# main.net
KiCad netlist of a schematic drawn in EAGLE
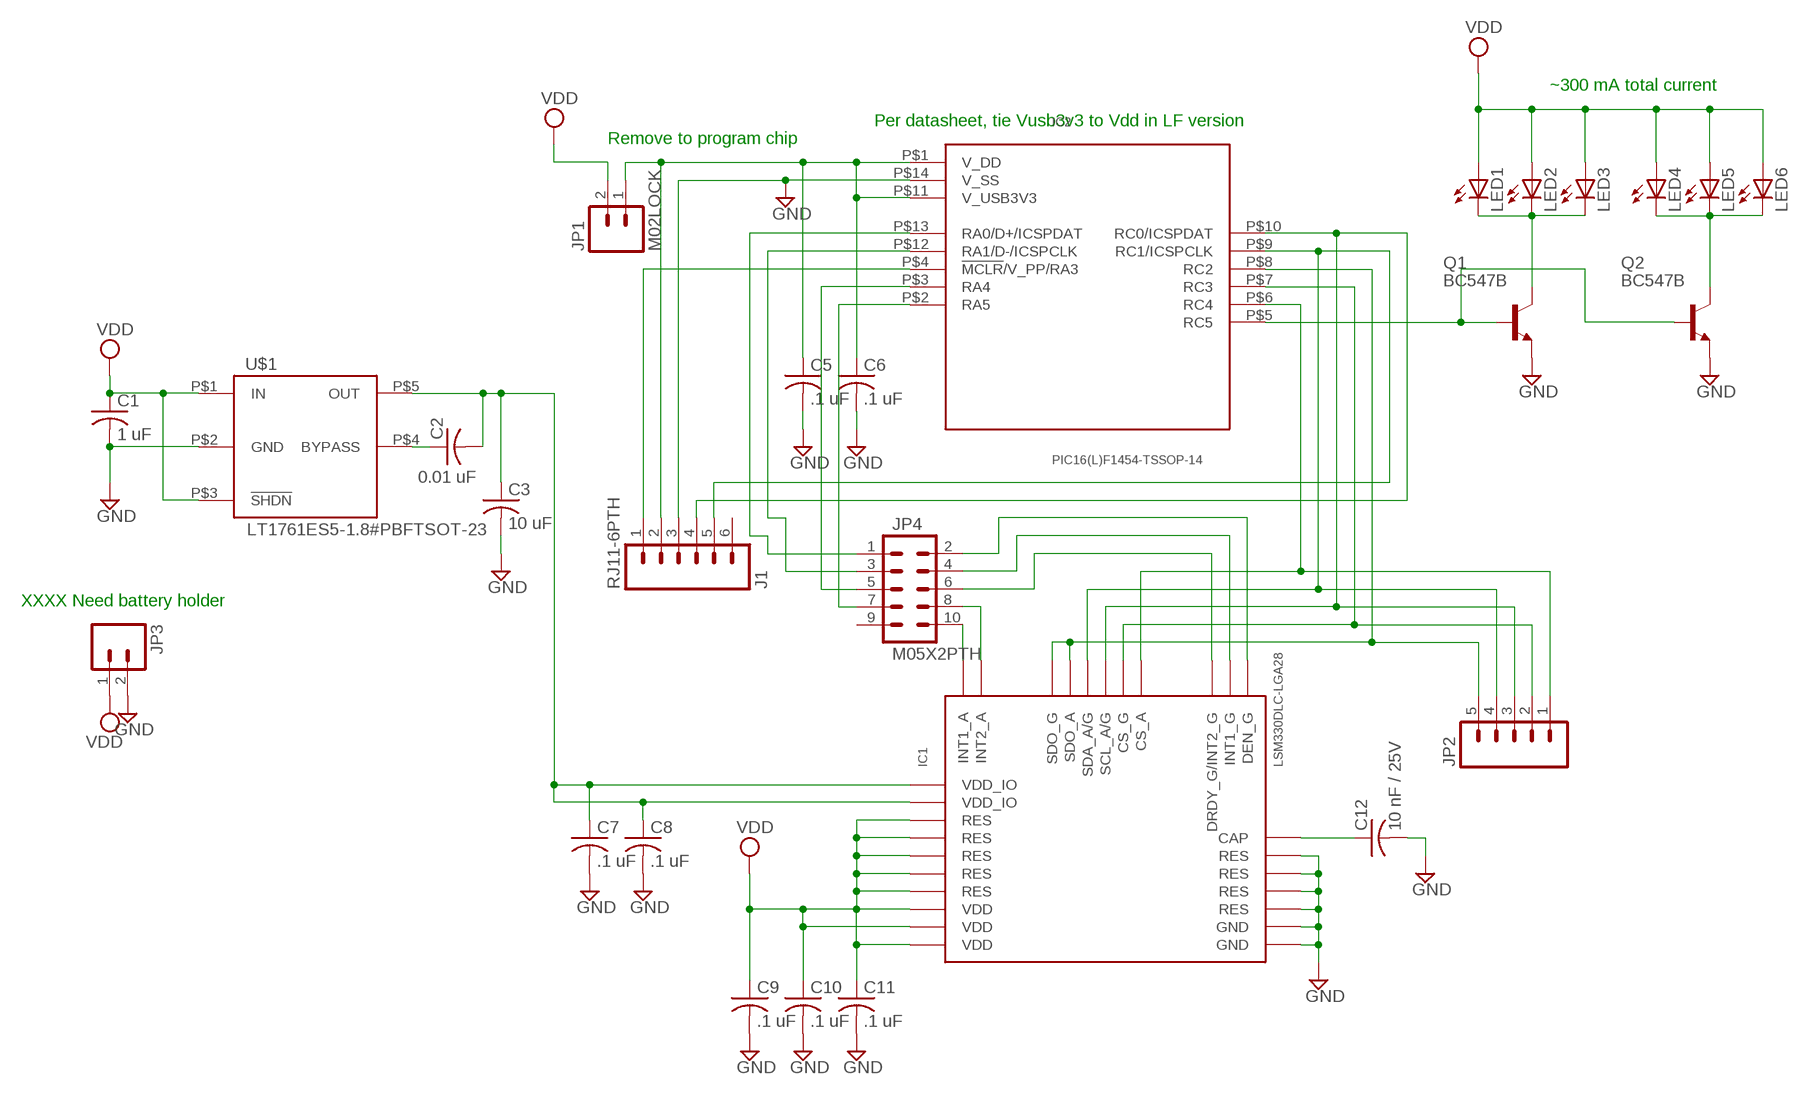
[diagram p0: schematic, sheet 1]

(export (version "E")
  (design (tool "Eeschema 10.0.6"))
  (components
    (comp (ref "C1")
      (value "1 uF")
      (footprint "eagle-import:C1206")
      (libsource (lib "eagle-import") (part "C-USC1206"))
    )
    (comp (ref "C2")
      (value "0.01 uF")
      (footprint "eagle-import:C1206")
      (libsource (lib "eagle-import") (part "C-USC1206"))
    )
    (comp (ref "C3")
      (value "10 uF")
      (footprint "eagle-import:C1206")
      (libsource (lib "eagle-import") (part "C-USC1206"))
    )
    (comp (ref "C5")
      (value ".1 uF")
      (footprint "eagle-import:C1206")
      (libsource (lib "eagle-import") (part "C-USC1206"))
    )
    (comp (ref "C6")
      (value ".1 uF")
      (footprint "eagle-import:C1206")
      (libsource (lib "eagle-import") (part "C-USC1206"))
    )
    (comp (ref "C7")
      (value ".1 uF")
      (footprint "eagle-import:C1206")
      (libsource (lib "eagle-import") (part "C-USC1206"))
    )
    (comp (ref "C8")
      (value ".1 uF")
      (footprint "eagle-import:C1206")
      (libsource (lib "eagle-import") (part "C-USC1206"))
    )
    (comp (ref "C9")
      (value ".1 uF")
      (footprint "eagle-import:C1206")
      (libsource (lib "eagle-import") (part "C-USC1206"))
    )
    (comp (ref "C10")
      (value ".1 uF")
      (footprint "eagle-import:C1206")
      (libsource (lib "eagle-import") (part "C-USC1206"))
    )
    (comp (ref "C11")
      (value ".1 uF")
      (footprint "eagle-import:C1206")
      (libsource (lib "eagle-import") (part "C-USC1206"))
    )
    (comp (ref "C12")
      (value "10 nF / 25V")
      (footprint "eagle-import:C1206")
      (libsource (lib "eagle-import") (part "C-USC1206"))
    )
    (comp (ref "IC1")
      (value "LSM330DLC-LGA28")
      (footprint "eagle-import:LGA-28")
      (libsource (lib "eagle-import") (part "LSM330DLC-LGA28"))
    )
    (comp (ref "IC2")
      (value "PIC16(L)F1454-TSSOP-14")
      (footprint "eagle-import:TSSOP-14")
      (libsource (lib "eagle-import") (part "PIC16(L)F1454-TSSOP-14"))
    )
    (comp (ref "J1")
      (value "RJ11-6PTH")
      (footprint "eagle-import:RJ11-6")
      (libsource (lib "eagle-import") (part "RJ11-6PTH"))
    )
    (comp (ref "JP1")
      (value "M02LOCK")
      (footprint "eagle-import:1X02_LOCK")
      (libsource (lib "eagle-import") (part "M02LOCK"))
    )
    (comp (ref "JP2")
      (value "M05PTH")
      (footprint "eagle-import:1X05")
      (libsource (lib "eagle-import") (part "M05PTH"))
    )
    (comp (ref "JP3")
      (value "M02LOCK")
      (footprint "eagle-import:1X02_LOCK")
      (libsource (lib "eagle-import") (part "M02LOCK"))
    )
    (comp (ref "JP4")
      (value "M05X2PTH")
      (footprint "eagle-import:AVR_ICSP")
      (libsource (lib "eagle-import") (part "M05X2PTH"))
    )
    (comp (ref "LED1")
      (value "LED5MM")
      (footprint "eagle-import:LED5MM")
      (libsource (lib "eagle-import") (part "LED5MM"))
    )
    (comp (ref "LED2")
      (value "LED5MM")
      (footprint "eagle-import:LED5MM")
      (libsource (lib "eagle-import") (part "LED5MM"))
    )
    (comp (ref "LED3")
      (value "LED5MM")
      (footprint "eagle-import:LED5MM")
      (libsource (lib "eagle-import") (part "LED5MM"))
    )
    (comp (ref "LED4")
      (value "LED5MM")
      (footprint "eagle-import:LED5MM")
      (libsource (lib "eagle-import") (part "LED5MM"))
    )
    (comp (ref "LED5")
      (value "LED5MM")
      (footprint "eagle-import:LED5MM")
      (libsource (lib "eagle-import") (part "LED5MM"))
    )
    (comp (ref "LED6")
      (value "LED5MM")
      (footprint "eagle-import:LED5MM")
      (libsource (lib "eagle-import") (part "LED5MM"))
    )
    (comp (ref "Q1")
      (value "BC547B")
      (footprint "eagle-import:TO92")
      (libsource (lib "eagle-import") (part "BC547B"))
    )
    (comp (ref "Q2")
      (value "BC547B")
      (footprint "eagle-import:TO92")
      (libsource (lib "eagle-import") (part "BC547B"))
    )
    (comp (ref "U$1")
      (value "LT1761ES5-1.8#PBFTSOT-23")
      (footprint "eagle-import:TSOT-23")
      (libsource (lib "eagle-import") (part "LT1761ES5-1.8#PBFTSOT-23"))
    )
  )
  (nets
    (net (code "1") (name "GND") (class "Default")
      (node (ref "C1") (pin "2") (pinfunction "2_2") (pintype "passive"))
      (node (ref "C10") (pin "2") (pinfunction "2_2") (pintype "passive"))
      (node (ref "C11") (pin "2") (pinfunction "2_2") (pintype "passive"))
      (node (ref "C12") (pin "2") (pinfunction "2_2") (pintype "passive"))
      (node (ref "C3") (pin "2") (pinfunction "2_2") (pintype "passive"))
      (node (ref "C5") (pin "2") (pinfunction "2_2") (pintype "passive"))
      (node (ref "C6") (pin "2") (pinfunction "2_2") (pintype "passive"))
      (node (ref "C7") (pin "2") (pinfunction "2_2") (pintype "passive"))
      (node (ref "C8") (pin "2") (pinfunction "2_2") (pintype "passive"))
      (node (ref "C9") (pin "2") (pinfunction "2_2") (pintype "passive"))
      (node (ref "IC1") (pin "P$1") (pinfunction "GND_P$1") (pintype "power_in"))
      (node (ref "IC1") (pin "P$2") (pinfunction "RES_P$2") (pintype "power_in"))
      (node (ref "IC1") (pin "P$3") (pinfunction "RES_P$3") (pintype "power_in"))
      (node (ref "IC1") (pin "P$4") (pinfunction "RES_P$4") (pintype "power_in"))
      (node (ref "IC1") (pin "P$5") (pinfunction "RES_P$5") (pintype "power_in"))
      (node (ref "IC1") (pin "P$6") (pinfunction "GND_P$6") (pintype "power_in"))
      (node (ref "IC2") (pin "P$14") (pinfunction "V_SS_P$14") (pintype "power_in"))
      (node (ref "J1") (pin "3") (pinfunction "3_3") (pintype "passive"))
      (node (ref "JP3") (pin "2") (pinfunction "2_2") (pintype "passive"))
      (node (ref "Q1") (pin "1") (pinfunction "E_1") (pintype "passive"))
      (node (ref "Q2") (pin "1") (pinfunction "E_1") (pintype "passive"))
      (node (ref "U$1") (pin "P$2") (pinfunction "GND_P$2") (pintype "power_in"))
    )
    (net (code "2") (name "Net-(IC1-CAP)") (class "Default")
      (node (ref "C12") (pin "1") (pinfunction "1_1") (pintype "passive"))
      (node (ref "IC1") (pin "P$15") (pinfunction "CAP_P$15") (pintype "passive"))
    )
    (net (code "3") (name "Net-(IC1-CS_A)") (class "Default")
      (node (ref "IC1") (pin "P$23") (pinfunction "CS_A_P$23") (pintype "bidirectional"))
      (node (ref "IC2") (pin "P$6") (pinfunction "RC4_P$6") (pintype "bidirectional"))
      (node (ref "JP2") (pin "1") (pinfunction "1_1") (pintype "passive"))
    )
    (net (code "4") (name "Net-(IC1-CS_G)") (class "Default")
      (node (ref "IC1") (pin "P$22") (pinfunction "CS_G_P$22") (pintype "bidirectional"))
      (node (ref "IC2") (pin "P$7") (pinfunction "RC3_P$7") (pintype "bidirectional"))
      (node (ref "JP2") (pin "2") (pinfunction "2_2") (pintype "passive"))
    )
    (net (code "5") (name "Net-(IC1-DEN_G)") (class "Default")
      (node (ref "IC1") (pin "P$16") (pinfunction "DEN_G_P$16") (pintype "bidirectional"))
      (node (ref "JP4") (pin "2") (pinfunction "2_2") (pintype "passive"))
    )
    (net (code "6") (name "Net-(IC1-DRDY_G{slash}INT2_G)") (class "Default")
      (node (ref "IC1") (pin "P$17") (pinfunction "DRDY_G/INT2_G_P$17") (pintype "bidirectional"))
      (node (ref "JP4") (pin "6") (pinfunction "6_6") (pintype "passive"))
    )
    (net (code "7") (name "Net-(IC1-INT1_A)") (class "Default")
      (node (ref "IC1") (pin "P$20") (pinfunction "INT1_A_P$20") (pintype "bidirectional"))
      (node (ref "JP4") (pin "10") (pinfunction "10_10") (pintype "passive"))
    )
    (net (code "8") (name "Net-(IC1-INT1_G)") (class "Default")
      (node (ref "IC1") (pin "P$18") (pinfunction "INT1_G_P$18") (pintype "bidirectional"))
      (node (ref "JP4") (pin "4") (pinfunction "4_4") (pintype "passive"))
    )
    (net (code "9") (name "Net-(IC1-INT2_A)") (class "Default")
      (node (ref "IC1") (pin "P$19") (pinfunction "INT2_A_P$19") (pintype "bidirectional"))
      (node (ref "JP4") (pin "8") (pinfunction "8_8") (pintype "passive"))
    )
    (net (code "10") (name "Net-(IC1-SCL_A{slash}G)") (class "Default")
      (node (ref "IC1") (pin "P$24") (pinfunction "SCL_A/G_P$24") (pintype "bidirectional"))
      (node (ref "IC2") (pin "P$10") (pinfunction "RC0/ICSPDAT_P$10") (pintype "bidirectional"))
      (node (ref "J1") (pin "4") (pinfunction "4_4") (pintype "passive"))
      (node (ref "JP2") (pin "3") (pinfunction "3_3") (pintype "passive"))
    )
    (net (code "11") (name "Net-(IC1-SDA_A{slash}G)") (class "Default")
      (node (ref "IC1") (pin "P$28") (pinfunction "SDA_A/G_P$28") (pintype "bidirectional"))
      (node (ref "IC2") (pin "P$9") (pinfunction "RC1/ICSPCLK_P$9") (pintype "bidirectional"))
      (node (ref "J1") (pin "5") (pinfunction "5_5") (pintype "passive"))
      (node (ref "JP2") (pin "4") (pinfunction "4_4") (pintype "passive"))
    )
    (net (code "12") (name "Net-(IC1-SDO_A)") (class "Default")
      (node (ref "IC1") (pin "P$26") (pinfunction "SDO_G_P$26") (pintype "bidirectional"))
      (node (ref "IC1") (pin "P$27") (pinfunction "SDO_A_P$27") (pintype "bidirectional"))
      (node (ref "IC2") (pin "P$8") (pinfunction "RC2_P$8") (pintype "bidirectional"))
      (node (ref "JP2") (pin "5") (pinfunction "5_5") (pintype "passive"))
    )
    (net (code "13") (name "Net-(IC2-RA0{slash}D+{slash}ICSPDAT)") (class "Default")
      (node (ref "IC2") (pin "P$13") (pinfunction "RA0/D+/ICSPDAT_P$13") (pintype "bidirectional"))
      (node (ref "JP4") (pin "1") (pinfunction "1_1") (pintype "passive"))
    )
    (net (code "14") (name "Net-(IC2-RA1{slash}D-{slash}ICSPCLK)") (class "Default")
      (node (ref "IC2") (pin "P$12") (pinfunction "RA1/D-/ICSPCLK_P$12") (pintype "bidirectional"))
      (node (ref "JP4") (pin "3") (pinfunction "3_3") (pintype "passive"))
    )
    (net (code "15") (name "Net-(IC2-RA4)") (class "Default")
      (node (ref "IC2") (pin "P$3") (pinfunction "RA4_P$3") (pintype "bidirectional"))
      (node (ref "JP4") (pin "5") (pinfunction "5_5") (pintype "passive"))
    )
    (net (code "16") (name "Net-(IC2-RA5)") (class "Default")
      (node (ref "IC2") (pin "P$2") (pinfunction "RA5_P$2") (pintype "bidirectional"))
      (node (ref "JP4") (pin "7") (pinfunction "7_7") (pintype "passive"))
    )
    (net (code "17") (name "Net-(IC2-RC5)") (class "Default")
      (node (ref "IC2") (pin "P$5") (pinfunction "RC5_P$5") (pintype "bidirectional"))
      (node (ref "Q1") (pin "2") (pinfunction "B_2") (pintype "passive"))
      (node (ref "Q2") (pin "2") (pinfunction "B_2") (pintype "passive"))
    )
    (net (code "18") (name "Net-(IC2-V_DD)") (class "Default")
      (node (ref "C5") (pin "1") (pinfunction "1_1") (pintype "passive"))
      (node (ref "C6") (pin "1") (pinfunction "1_1") (pintype "passive"))
      (node (ref "IC2") (pin "P$1") (pinfunction "V_DD_P$1") (pintype "power_in"))
      (node (ref "IC2") (pin "P$11") (pinfunction "V_USB3V3_P$11") (pintype "power_in"))
      (node (ref "J1") (pin "2") (pinfunction "2_2") (pintype "passive"))
      (node (ref "JP1") (pin "1") (pinfunction "1_1") (pintype "passive"))
    )
    (net (code "19") (name "Net-(IC2-~{MCLR}{slash}V_PP{slash}RA3)") (class "Default")
      (node (ref "IC2") (pin "P$4") (pinfunction "~{MCLR}/V_PP/RA3_P$4") (pintype "bidirectional"))
      (node (ref "J1") (pin "1") (pinfunction "1_1") (pintype "passive"))
    )
    (net (code "20") (name "Net-(LED1-C)") (class "Default")
      (node (ref "LED1") (pin "K") (pinfunction "C_K") (pintype "passive"))
      (node (ref "LED2") (pin "K") (pinfunction "C_K") (pintype "passive"))
      (node (ref "LED3") (pin "K") (pinfunction "C_K") (pintype "passive"))
      (node (ref "Q1") (pin "3") (pinfunction "C_3") (pintype "passive"))
    )
    (net (code "21") (name "Net-(LED4-C)") (class "Default")
      (node (ref "LED4") (pin "K") (pinfunction "C_K") (pintype "passive"))
      (node (ref "LED5") (pin "K") (pinfunction "C_K") (pintype "passive"))
      (node (ref "LED6") (pin "K") (pinfunction "C_K") (pintype "passive"))
      (node (ref "Q2") (pin "3") (pinfunction "C_3") (pintype "passive"))
    )
    (net (code "22") (name "Net-(U$1-BYPASS)") (class "Default")
      (node (ref "C2") (pin "1") (pinfunction "1_1") (pintype "passive"))
      (node (ref "U$1") (pin "P$4") (pinfunction "BYPASS_P$4") (pintype "output"))
    )
    (net (code "23") (name "Net-(U$1-OUT)") (class "Default")
      (node (ref "C2") (pin "2") (pinfunction "2_2") (pintype "passive"))
      (node (ref "C3") (pin "1") (pinfunction "1_1") (pintype "passive"))
      (node (ref "C7") (pin "1") (pinfunction "1_1") (pintype "passive"))
      (node (ref "C8") (pin "1") (pinfunction "1_1") (pintype "passive"))
      (node (ref "IC1") (pin "P$21") (pinfunction "VDD_IO_P$21") (pintype "power_in"))
      (node (ref "IC1") (pin "P$25") (pinfunction "VDD_IO_P$25") (pintype "bidirectional"))
      (node (ref "U$1") (pin "P$5") (pinfunction "OUT_P$5") (pintype "power_in"))
    )
    (net (code "24") (name "VDD") (class "Default")
      (node (ref "C1") (pin "1") (pinfunction "1_1") (pintype "passive"))
      (node (ref "C10") (pin "1") (pinfunction "1_1") (pintype "passive"))
      (node (ref "C11") (pin "1") (pinfunction "1_1") (pintype "passive"))
      (node (ref "C9") (pin "1") (pinfunction "1_1") (pintype "passive"))
      (node (ref "IC1") (pin "P$10") (pinfunction "RES_P$10") (pintype "power_in"))
      (node (ref "IC1") (pin "P$11") (pinfunction "RES_P$11") (pintype "power_in"))
      (node (ref "IC1") (pin "P$12") (pinfunction "RES_P$12") (pintype "power_in"))
      (node (ref "IC1") (pin "P$13") (pinfunction "RES_P$13") (pintype "power_in"))
      (node (ref "IC1") (pin "P$14") (pinfunction "RES_P$14") (pintype "power_in"))
      (node (ref "IC1") (pin "P$7") (pinfunction "VDD_P$7") (pintype "power_in"))
      (node (ref "IC1") (pin "P$8") (pinfunction "VDD_P$8") (pintype "power_in"))
      (node (ref "IC1") (pin "P$9") (pinfunction "VDD_P$9") (pintype "power_in"))
      (node (ref "JP1") (pin "2") (pinfunction "2_2") (pintype "passive"))
      (node (ref "JP3") (pin "1") (pinfunction "1_1") (pintype "passive"))
      (node (ref "LED1") (pin "A") (pinfunction "A_A") (pintype "passive"))
      (node (ref "LED2") (pin "A") (pinfunction "A_A") (pintype "passive"))
      (node (ref "LED3") (pin "A") (pinfunction "A_A") (pintype "passive"))
      (node (ref "LED4") (pin "A") (pinfunction "A_A") (pintype "passive"))
      (node (ref "LED5") (pin "A") (pinfunction "A_A") (pintype "passive"))
      (node (ref "LED6") (pin "A") (pinfunction "A_A") (pintype "passive"))
      (node (ref "U$1") (pin "P$1") (pinfunction "IN_P$1") (pintype "power_in"))
      (node (ref "U$1") (pin "P$3") (pinfunction "~{SHDN}_P$3") (pintype "input"))
    )
    (net (code "25") (name "unconnected-(J1-Pad6)") (class "Default")
      (node (ref "J1") (pin "6") (pinfunction "6_6") (pintype "passive"))
    )
    (net (code "26") (name "unconnected-(JP4-Pad9)") (class "Default")
      (node (ref "JP4") (pin "9") (pinfunction "9_9") (pintype "passive"))
    )
  )
)
